# NODE_Misc_V2.net
KiCad netlist of a schematic drawn in Altium Designer
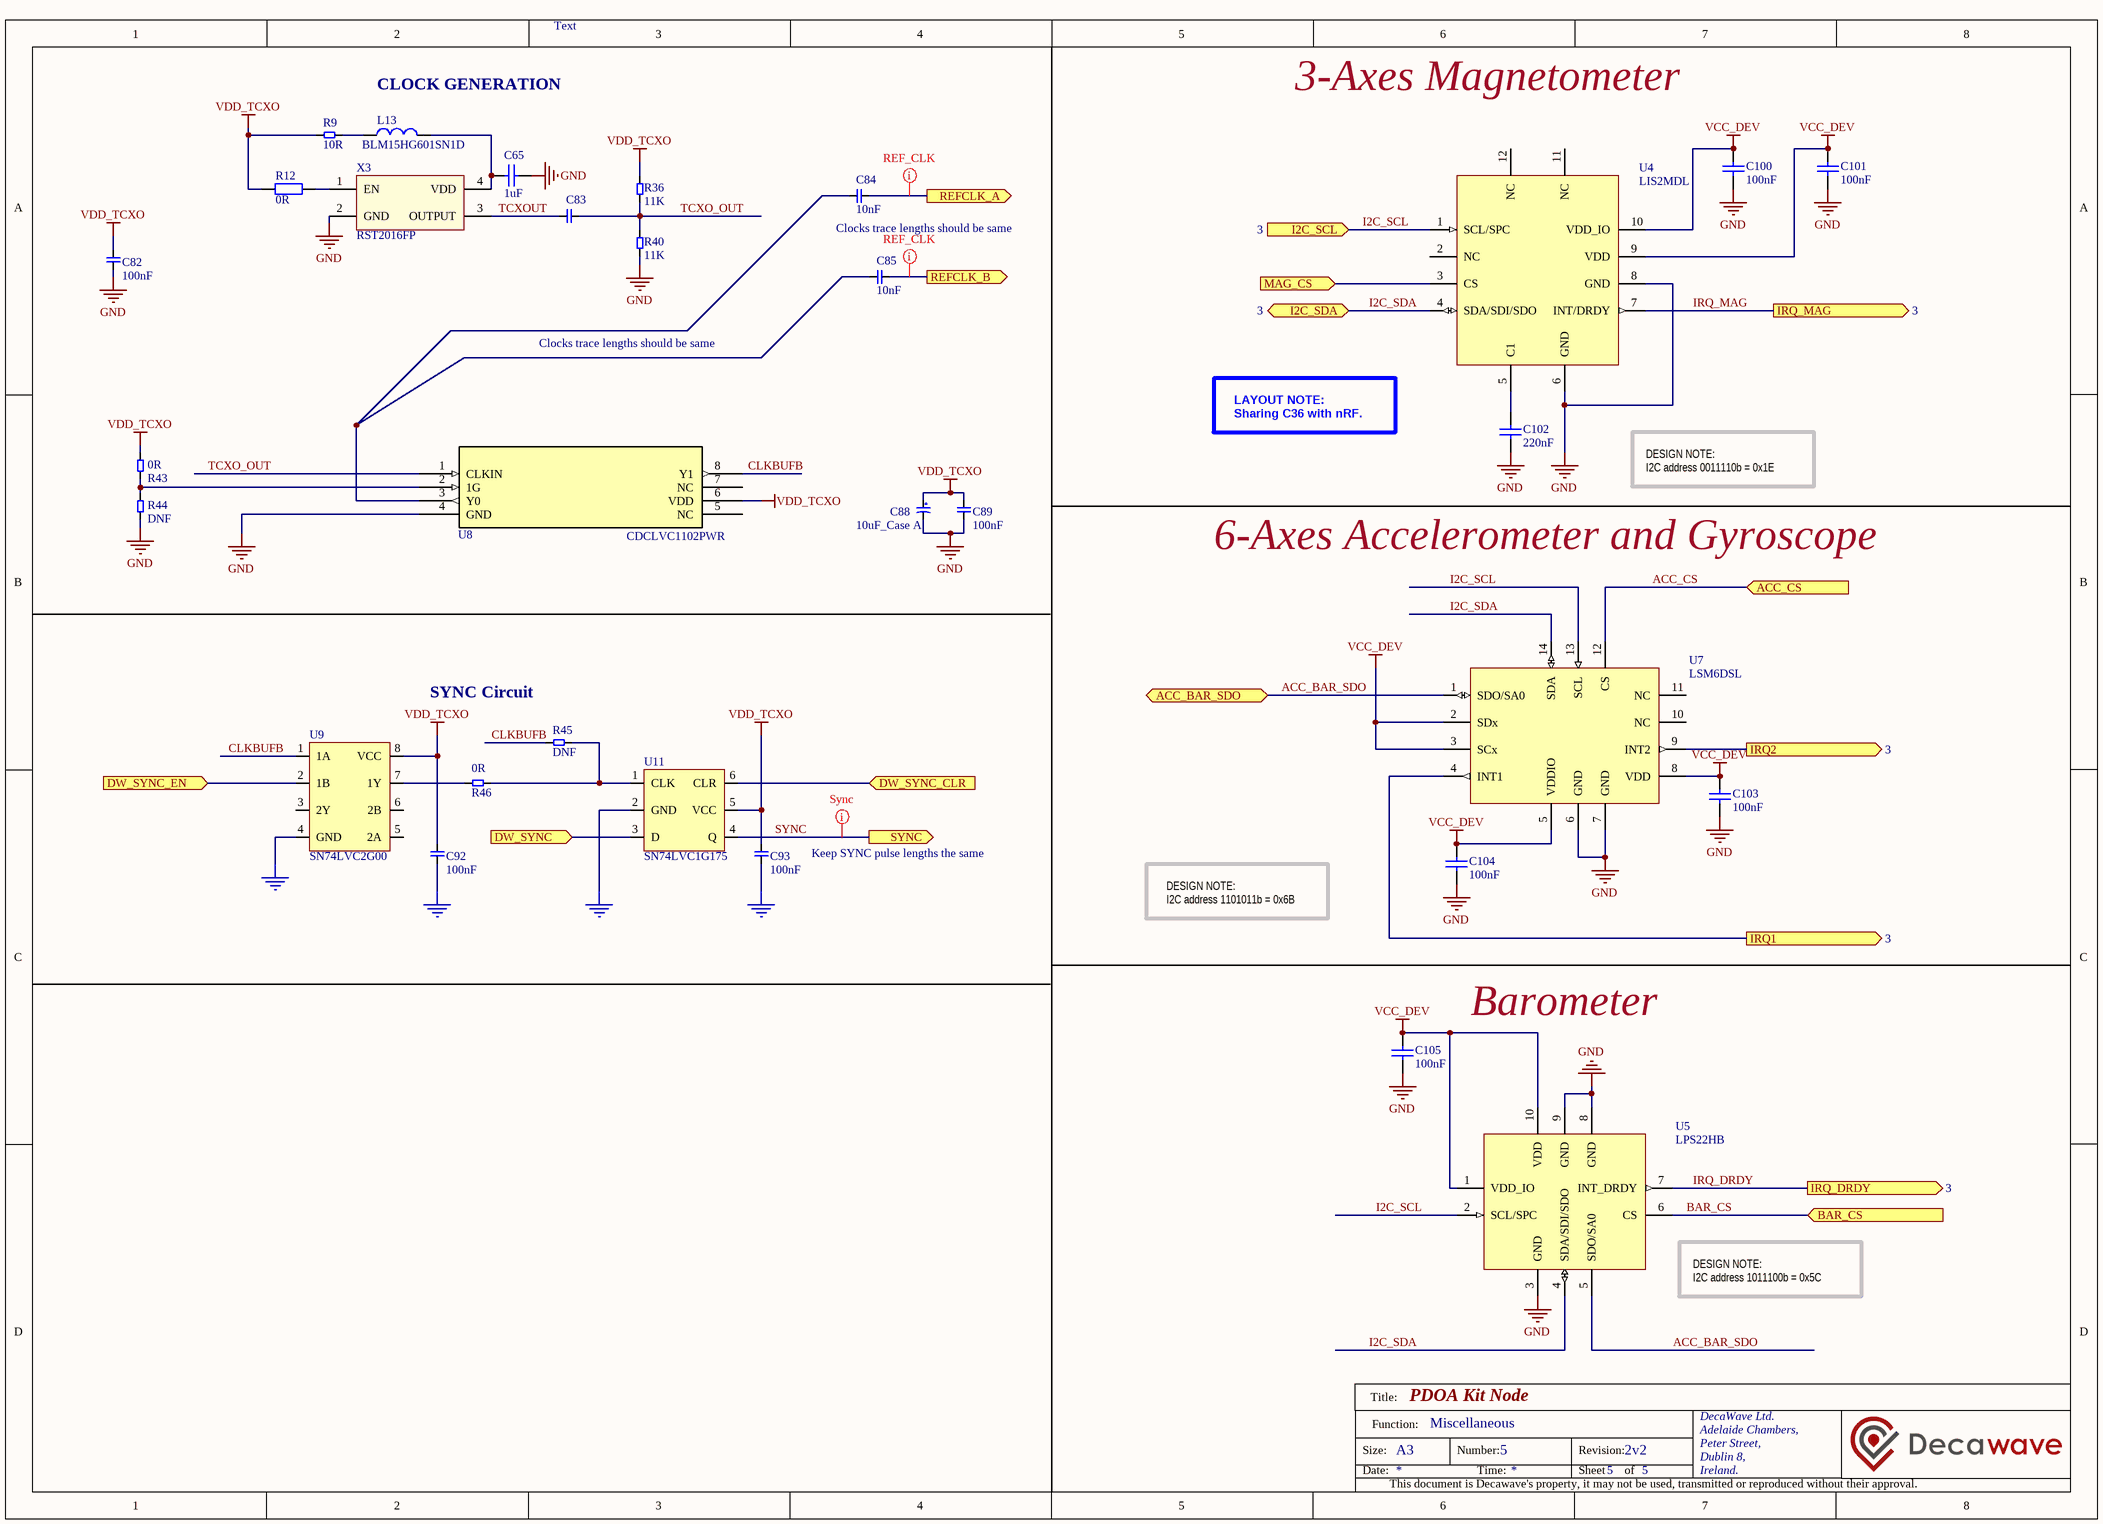
[diagram p0: NODE_Misc_V2.SchDoc]

(export (version "E")
  (design (tool "Eeschema 10.0.6"))
  (components
    (comp (ref "C65")
      (value "1uF")
      (footprint "C0402")
      (description "CAP CER 1UF 10V X5R 0402")
      (fields
        (field (name "MANUFACTURER") "Murata Electronics North America")
        (field (name "MANUFACTURER PART NUMBER") "GRM155R61A105KE15D")
      )
      (libsource (lib "drak_Library") (part "GRM155R61A105KE15D"))
    )
    (comp (ref "C82")
      (value "100nF")
      (footprint "C0201")
      (description "100nF_0201_10%")
      (fields
        (field (name "MANUFACTURER") "Murata Electronics North America")
        (field (name "MANUFACTURER PART NUMBER") "GRM033C81E104KE14D")
      )
      (libsource (lib "DecaWavedB") (part "Capacitor - non polarized"))
    )
    (comp (ref "C83")
      (value "1nF")
      (footprint "C0402")
      (description "1nF_0402_10%")
      (fields
        (field (name "MANUFACTURER PART NUMBER") "GRM155R71H102KA01D")
        (field (name "MANUFACTURER") "Murata Electronics North America")
      )
      (libsource (lib "DecaWavedB") (part "Capacitor - non polarized"))
    )
    (comp (ref "C84")
      (value "10nF")
      (footprint "C0201")
      (description "10nF_0201_10%")
      (fields
        (field (name "MANUFACTURER") "Murata Electronics North America")
        (field (name "MANUFACTURER PART NUMBER") "GRM033R61E103KA12D")
      )
      (libsource (lib "DecaWavedB") (part "Capacitor - non polarized"))
    )
    (comp (ref "C85")
      (value "10nF")
      (footprint "C0201")
      (description "10nF_0201_10%")
      (fields
        (field (name "MANUFACTURER") "Murata Electronics North America")
        (field (name "MANUFACTURER PART NUMBER") "GRM033R61E103KA12D")
      )
      (libsource (lib "DecaWavedB") (part "Capacitor - non polarized"))
    )
    (comp (ref "C88")
      (value "10uF_Case A")
      (footprint "TANT3216")
      (description "10uF_CaseA_10%")
      (fields
        (field (name "MANUFACTURER PART NUMBER") "293D106X9016A2TE3")
        (field (name "MANUFACTURER") "Vishay")
      )
      (libsource (lib "DecaWavedB") (part "Capacitor - polarized"))
    )
    (comp (ref "C89")
      (value "100nF")
      (footprint "C0201")
      (description "100nF_0201_10%")
      (fields
        (field (name "MANUFACTURER") "Murata Electronics North America")
        (field (name "MANUFACTURER PART NUMBER") "GRM033C81E104KE14D")
      )
      (libsource (lib "DecaWavedB") (part "Capacitor - non polarized"))
    )
    (comp (ref "C92")
      (value "100nF")
      (footprint "C0201")
      (description "100nF_0201_10%")
      (fields
        (field (name "MANUFACTURER") "Murata Electronics North America")
        (field (name "MANUFACTURER PART NUMBER") "GRM033C81E104KE14D")
      )
      (libsource (lib "DecaWavedB") (part "Capacitor - non polarized"))
    )
    (comp (ref "C93")
      (value "100nF")
      (footprint "C0201")
      (description "100nF_0201_10%")
      (fields
        (field (name "MANUFACTURER") "Murata Electronics North America")
        (field (name "MANUFACTURER PART NUMBER") "GRM033C81E104KE14D")
      )
      (libsource (lib "DecaWavedB") (part "Capacitor - non polarized"))
    )
    (comp (ref "C100")
      (value "100nF")
      (footprint "C0201")
      (description "100nF_0201_10%")
      (fields
        (field (name "MANUFACTURER") "Murata Electronics North America")
        (field (name "MANUFACTURER PART NUMBER") "GRM033C81E104KE14D")
      )
      (libsource (lib "drak_Library") (part "GRM033C81E104ME14D"))
    )
    (comp (ref "C101")
      (value "100nF")
      (footprint "C0201")
      (description "100nF_0201_10%")
      (fields
        (field (name "MANUFACTURER") "Murata Electronics North America")
        (field (name "MANUFACTURER PART NUMBER") "GRM033C81E104KE14D")
      )
      (libsource (lib "drak_Library") (part "GRM033C81E104ME14D"))
    )
    (comp (ref "C102")
      (value "220nF")
      (footprint "C0201")
      (description "CAP CER 220nF 25V X6S 0201")
      (fields
        (field (name "MANUFACTURER") "Murata Electronics North America")
        (field (name "MANUFACTURER PART NUMBER") "GRM033R61A224KE90D")
      )
      (libsource (lib "drak_Library") (part "GRM033C81E104ME14D"))
    )
    (comp (ref "C103")
      (value "100nF")
      (footprint "C0201")
      (description "100nF_0201_10%")
      (fields
        (field (name "MANUFACTURER") "Murata Electronics North America")
        (field (name "MANUFACTURER PART NUMBER") "GRM033C81E104KE14D")
      )
      (libsource (lib "drak_Library") (part "GRM033C81E104ME14D"))
    )
    (comp (ref "C104")
      (value "100nF")
      (footprint "C0201")
      (description "100nF_0201_10%")
      (fields
        (field (name "MANUFACTURER") "Murata Electronics North America")
        (field (name "MANUFACTURER PART NUMBER") "GRM033C81E104KE14D")
      )
      (libsource (lib "drak_Library") (part "GRM033C81E104ME14D"))
    )
    (comp (ref "C105")
      (value "100nF")
      (footprint "C0201")
      (description "100nF_0201_10%")
      (fields
        (field (name "MANUFACTURER") "Murata Electronics North America")
        (field (name "MANUFACTURER PART NUMBER") "GRM033C81E104KE14D")
      )
      (libsource (lib "drak_Library") (part "GRM033C81E104ME14D"))
    )
    (comp (ref "L13")
      (value "BLM15HG601SN1D")
      (footprint "L0402")
      (description "FERRITE BEAD, 0.7OHM, 300MA, 0402")
      (fields (field (name "MANUFACTURER") "Murata Electronics North America"))
      (libsource (lib "DecaWavedB") (part "inductor"))
    )
    (comp (ref "R9")
      (value "10R")
      (footprint "R0201")
      (description "10R_0201_1%")
      (fields
        (field (name "MANUFACTURER PART NUMBER") "RC0201FR-0710RL")
        (field (name "MANUFACTURER") "Yageo")
      )
      (libsource (lib "DecaWavedB") (part "Resistor"))
    )
    (comp (ref "R12")
      (value "0R")
      (footprint "R0201")
      (description "RES SMD 0.0OHM JUMPER 1/20W 0201")
      (fields
        (field (name "MANUFACTURER") "Yageo")
        (field (name "MANUFACTURER PART NUMBER") "RC0201JR-070RL")
      )
      (libsource (lib "drak_Library") (part "RC0201JR-070RL"))
    )
    (comp (ref "R36")
      (value "11K")
      (footprint "R0201")
      (description "11K_0201_1%")
      (fields
        (field (name "MANUFACTURER") "Yageo")
        (field (name "MANUFACTURER PART NUMBER") "RC0201FR-0711KL")
      )
      (libsource (lib "DecaWavedB") (part "Resistor"))
    )
    (comp (ref "R40")
      (value "11K")
      (footprint "R0201")
      (description "11K_0201_1%")
      (fields
        (field (name "MANUFACTURER") "Yageo")
        (field (name "MANUFACTURER PART NUMBER") "RC0201FR-0711KL")
      )
      (libsource (lib "DecaWavedB") (part "Resistor"))
    )
    (comp (ref "R43")
      (value "0R")
      (footprint "R0201")
      (description "RES SMD 0.0OHM JUMPER 1/20W 0201")
      (fields
        (field (name "MANUFACTURER PART NUMBER") "RC0201JR-070RL")
        (field (name "MANUFACTURER") "Yageo")
      )
      (libsource (lib "DecaWavedB") (part "Resistor"))
    )
    (comp (ref "R44") (value "DNF") (footprint "R0201") (libsource (lib "DecaWavedB") (part "Resistor")))
    (comp (ref "R45") (value "DNF") (footprint "R0201") (libsource (lib "DecaWavedB") (part "Resistor")))
    (comp (ref "R46")
      (value "0R")
      (footprint "R0201")
      (description "RES SMD 0.0OHM JUMPER 1/20W 0201")
      (fields
        (field (name "MANUFACTURER PART NUMBER") "RC0201JR-070RL")
        (field (name "MANUFACTURER") "Yageo")
      )
      (libsource (lib "DecaWavedB") (part "Resistor"))
    )
    (comp (ref "U4")
      (value "LIS2MDL")
      (footprint "IC_LGA-12")
      (fields
        (field (name "MANUFACTURER") "STmicroelectronics")
        (field (name "MANUFACTURER PART NUMBER") "LIS2MDLTR")
      )
      (libsource (lib "LGA12_LGA14_LIB") (part "LIS2MDL"))
    )
    (comp (ref "U5")
      (value "LPS22HB")
      (footprint "HLGA-10L")
      (fields
        (field (name "MANUFACTURER") "STmicroelectronics")
        (field (name "MANUFACTURER PART NUMBER") "LPS22HBTR")
      )
      (libsource (lib "LGA12_LGA14_LIB") (part "LPS22HB"))
    )
    (comp (ref "U7")
      (value "LSM6DSL")
      (footprint "IC_LGA-14")
      (fields
        (field (name "MANUFACTURER") "STmicroelectronics")
        (field (name "MANUFACTURER PART NUMBER") "LSM6DSLTR")
      )
      (libsource (lib "LGA12_LGA14_LIB") (part "LSM6DSL"))
    )
    (comp (ref "U8")
      (value "CDCLVC1102")
      (footprint "TSSOP8_0P65_4P5X3P4")
      (description "Low Jitter,1:2 LVCMOS Fan-out Clock Buffer")
      (fields (field (name "MANUFACTURER") "TI") (field (name "MANUFACTURER PART NUMBER") "CDCLVC1102PWR"))
      (libsource (lib "DecaWavedB") (part "CDCLVC1102"))
    )
    (comp (ref "U9")
      (value "SN74LVC2G00")
      (footprint "VSSOP8_0P5_2P1X2P4")
      (description "2 Input NAND")
      (fields (field (name "MANUFACTURER PART NUMBER") "SN74LVC2G00DCU") (field (name "MANUFACTURER") "TI"))
      (libsource (lib "DecaWavedB") (part "SN74LVC2G00"))
    )
    (comp (ref "U11")
      (value "SN74LVC1G175")
      (footprint "SC70-6_0P65_2P15X1P4")
      (description "Single D-Type Flip Flop with Async Clear")
      (fields (field (name "MANUFACTURER PART NUMBER") "SN74LVC1G175DCK") (field (name "MANUFACTURER") "TI"))
      (libsource (lib "DecaWavedB") (part "SN74LVC1G175"))
    )
    (comp (ref "X3")
      (value "RST2016FP")
      (footprint "CAT567")
      (description "CRYSTAL TXCO RST2016FP")
      (fields (field (name "MANUFACTURER") "Rakon"))
      (libsource (lib "LGA12_LGA14_LIB") (part "RST2016FP"))
    )
  )
  (nets
    (net (code "1") (name "/ACC_BAR_SDO") (class "Default")
      (node (ref "U5") (pin "5") (pinfunction "SDO/SA0_5") (pintype "passive"))
      (node (ref "U7") (pin "1") (pinfunction "SDO/SA0_1") (pintype "bidirectional"))
    )
    (net (code "2") (name "/ACC_CS") (class "Default")
      (node (ref "U7") (pin "12") (pinfunction "CS_12") (pintype "passive"))
    )
    (net (code "3") (name "/BAR_CS") (class "Default")
      (node (ref "U5") (pin "6") (pinfunction "CS_6") (pintype "passive"))
    )
    (net (code "4") (name "/CLKBUFB") (class "Default")
      (node (ref "R45") (pin "2") (pinfunction "2_2") (pintype "passive"))
      (node (ref "U8") (pin "8") (pinfunction "Y1_8") (pintype "output"))
      (node (ref "U9") (pin "1") (pinfunction "1A_1") (pintype "passive"))
    )
    (net (code "5") (name "/DW_SYNC") (class "Default")
      (node (ref "U11") (pin "3") (pinfunction "D_3") (pintype "passive"))
    )
    (net (code "6") (name "/DW_SYNC_CLR") (class "Default")
      (node (ref "U11") (pin "6") (pinfunction "CLR_6") (pintype "passive"))
    )
    (net (code "7") (name "/DW_SYNC_EN") (class "Default")
      (node (ref "U9") (pin "2") (pinfunction "1B_2") (pintype "passive"))
    )
    (net (code "8") (name "/I2C_SCL") (class "Default")
      (node (ref "U4") (pin "1") (pinfunction "SCL/SPC_1") (pintype "input"))
      (node (ref "U5") (pin "2") (pinfunction "SCL/SPC_2") (pintype "input"))
      (node (ref "U7") (pin "13") (pinfunction "SCL_13") (pintype "input"))
    )
    (net (code "9") (name "/I2C_SDA") (class "Default")
      (node (ref "U4") (pin "4") (pinfunction "SDA/SDI/SDO_4") (pintype "bidirectional"))
      (node (ref "U5") (pin "4") (pinfunction "SDA/SDI/SDO_4") (pintype "bidirectional"))
      (node (ref "U7") (pin "14") (pinfunction "SDA_14") (pintype "bidirectional"))
    )
    (net (code "10") (name "/IRQ1") (class "Default")
      (node (ref "U7") (pin "4") (pinfunction "INT1_4") (pintype "output"))
    )
    (net (code "11") (name "/IRQ2") (class "Default")
      (node (ref "U7") (pin "9") (pinfunction "INT2_9") (pintype "output"))
    )
    (net (code "12") (name "/IRQ_DRDY") (class "Default")
      (node (ref "U5") (pin "7") (pinfunction "INT_DRDY_7") (pintype "output"))
    )
    (net (code "13") (name "/IRQ_MAG") (class "Default")
      (node (ref "U4") (pin "7") (pinfunction "INT/DRDY_7") (pintype "output"))
    )
    (net (code "14") (name "/MAG_CS") (class "Default")
      (node (ref "U4") (pin "3") (pinfunction "CS_3") (pintype "passive"))
    )
    (net (code "15") (name "/REFCLK_A") (class "Default")
      (node (ref "C84") (pin "1") (pinfunction "1_1") (pintype "passive"))
    )
    (net (code "16") (name "/REFCLK_B") (class "Default")
      (node (ref "C85") (pin "1") (pinfunction "1_1") (pintype "passive"))
    )
    (net (code "17") (name "/SYNC") (class "Default")
      (node (ref "U11") (pin "4") (pinfunction "Q_4") (pintype "passive"))
    )
    (net (code "18") (name "/TCXOUT") (class "Default")
      (node (ref "C83") (pin "1") (pinfunction "1_1") (pintype "passive"))
      (node (ref "X3") (pin "3") (pinfunction "OUTPUT_3") (pintype "passive"))
    )
    (net (code "19") (name "/TCXO_OUT") (class "Default")
      (node (ref "C83") (pin "2") (pinfunction "2_2") (pintype "passive"))
      (node (ref "R36") (pin "1") (pinfunction "1_1") (pintype "passive"))
      (node (ref "R40") (pin "2") (pinfunction "2_2") (pintype "passive"))
      (node (ref "U8") (pin "1") (pinfunction "CLKIN_1") (pintype "input"))
    )
    (net (code "20") (name "GND") (class "Default")
      (node (ref "C100") (pin "1") (pinfunction "1_1") (pintype "passive"))
      (node (ref "C101") (pin "1") (pinfunction "1_1") (pintype "passive"))
      (node (ref "C102") (pin "1") (pinfunction "1_1") (pintype "passive"))
      (node (ref "C103") (pin "1") (pinfunction "1_1") (pintype "passive"))
      (node (ref "C104") (pin "1") (pinfunction "1_1") (pintype "passive"))
      (node (ref "C105") (pin "1") (pinfunction "1_1") (pintype "passive"))
      (node (ref "C65") (pin "1") (pinfunction "1_1") (pintype "passive"))
      (node (ref "C82") (pin "1") (pinfunction "1_1") (pintype "passive"))
      (node (ref "C88") (pin "2") (pinfunction "2_2") (pintype "passive"))
      (node (ref "C89") (pin "1") (pinfunction "1_1") (pintype "passive"))
      (node (ref "C92") (pin "1") (pinfunction "1_1") (pintype "passive"))
      (node (ref "C93") (pin "1") (pinfunction "1_1") (pintype "passive"))
      (node (ref "R40") (pin "1") (pinfunction "1_1") (pintype "passive"))
      (node (ref "R44") (pin "1") (pinfunction "1_1") (pintype "passive"))
      (node (ref "U11") (pin "2") (pinfunction "GND_2") (pintype "passive"))
      (node (ref "U4") (pin "6") (pinfunction "GND_6") (pintype "passive"))
      (node (ref "U4") (pin "8") (pinfunction "GND_8") (pintype "passive"))
      (node (ref "U5") (pin "3") (pinfunction "GND_3") (pintype "passive"))
      (node (ref "U5") (pin "8") (pinfunction "GND_8") (pintype "passive"))
      (node (ref "U5") (pin "9") (pinfunction "GND_9") (pintype "passive"))
      (node (ref "U7") (pin "6") (pinfunction "GND_6") (pintype "passive"))
      (node (ref "U7") (pin "7") (pinfunction "GND_7") (pintype "passive"))
      (node (ref "U8") (pin "4") (pinfunction "GND_4") (pintype "power_in"))
      (node (ref "U9") (pin "4") (pinfunction "GND_4") (pintype "passive"))
      (node (ref "X3") (pin "2") (pinfunction "GND_2") (pintype "passive"))
    )
    (net (code "21") (name "Net-(L13-Pad1)") (class "Default")
      (node (ref "L13") (pin "1") (pinfunction "1_1") (pintype "passive"))
      (node (ref "R9") (pin "1") (pinfunction "1_1") (pintype "passive"))
    )
    (net (code "22") (name "Net-(U4-C1)") (class "Default")
      (node (ref "C102") (pin "2") (pinfunction "2_2") (pintype "passive"))
      (node (ref "U4") (pin "5") (pinfunction "C1_5") (pintype "passive"))
    )
    (net (code "23") (name "Net-(U8-1G)") (class "Default")
      (node (ref "R43") (pin "2") (pinfunction "2_2") (pintype "passive"))
      (node (ref "R44") (pin "2") (pinfunction "2_2") (pintype "passive"))
      (node (ref "U8") (pin "2") (pinfunction "1G_2") (pintype "input"))
    )
    (net (code "24") (name "Net-(U8-Y0)") (class "Default")
      (node (ref "C84") (pin "2") (pinfunction "2_2") (pintype "passive"))
      (node (ref "C85") (pin "2") (pinfunction "2_2") (pintype "passive"))
      (node (ref "U8") (pin "3") (pinfunction "Y0_3") (pintype "output"))
    )
    (net (code "25") (name "Net-(U9-1Y)") (class "Default")
      (node (ref "R46") (pin "2") (pinfunction "2_2") (pintype "passive"))
      (node (ref "U9") (pin "7") (pinfunction "1Y_7") (pintype "passive"))
    )
    (net (code "26") (name "Net-(U11-CLK)") (class "Default")
      (node (ref "R45") (pin "1") (pinfunction "1_1") (pintype "passive"))
      (node (ref "R46") (pin "1") (pinfunction "1_1") (pintype "passive"))
      (node (ref "U11") (pin "1") (pinfunction "CLK_1") (pintype "passive"))
    )
    (net (code "27") (name "Net-(X3-EN)") (class "Default")
      (node (ref "R12") (pin "2") (pinfunction "2_2") (pintype "passive"))
      (node (ref "X3") (pin "1") (pinfunction "EN_1") (pintype "passive"))
    )
    (net (code "28") (name "Net-(X3-VDD)") (class "Default")
      (node (ref "C65") (pin "2") (pinfunction "2_2") (pintype "passive"))
      (node (ref "L13") (pin "2") (pinfunction "2_2") (pintype "passive"))
      (node (ref "X3") (pin "4") (pinfunction "VDD_4") (pintype "passive"))
    )
    (net (code "29") (name "VCC_DEV") (class "Default")
      (node (ref "C100") (pin "2") (pinfunction "2_2") (pintype "passive"))
      (node (ref "C101") (pin "2") (pinfunction "2_2") (pintype "passive"))
      (node (ref "C103") (pin "2") (pinfunction "2_2") (pintype "passive"))
      (node (ref "C104") (pin "2") (pinfunction "2_2") (pintype "passive"))
      (node (ref "C105") (pin "2") (pinfunction "2_2") (pintype "passive"))
      (node (ref "U4") (pin "10") (pinfunction "VDD_IO_10") (pintype "power_in"))
      (node (ref "U4") (pin "9") (pinfunction "VDD_9") (pintype "power_in"))
      (node (ref "U5") (pin "1") (pinfunction "VDD_IO_1") (pintype "power_in"))
      (node (ref "U5") (pin "10") (pinfunction "VDD_10") (pintype "power_in"))
      (node (ref "U7") (pin "2") (pinfunction "SDx_2") (pintype "passive"))
      (node (ref "U7") (pin "3") (pinfunction "SCx_3") (pintype "passive"))
      (node (ref "U7") (pin "5") (pinfunction "VDDIO_5") (pintype "power_in"))
      (node (ref "U7") (pin "8") (pinfunction "VDD_8") (pintype "power_in"))
    )
    (net (code "30") (name "VDD_TCXO") (class "Default")
      (node (ref "C82") (pin "2") (pinfunction "2_2") (pintype "passive"))
      (node (ref "C88") (pin "1") (pinfunction "1_1") (pintype "passive"))
      (node (ref "C89") (pin "2") (pinfunction "2_2") (pintype "passive"))
      (node (ref "C92") (pin "2") (pinfunction "2_2") (pintype "passive"))
      (node (ref "C93") (pin "2") (pinfunction "2_2") (pintype "passive"))
      (node (ref "R12") (pin "1") (pinfunction "1_1") (pintype "passive"))
      (node (ref "R36") (pin "2") (pinfunction "2_2") (pintype "passive"))
      (node (ref "R43") (pin "1") (pinfunction "1_1") (pintype "passive"))
      (node (ref "R9") (pin "2") (pinfunction "2_2") (pintype "passive"))
      (node (ref "U11") (pin "5") (pinfunction "VCC_5") (pintype "passive"))
      (node (ref "U8") (pin "6") (pinfunction "VDD_6") (pintype "power_in"))
      (node (ref "U9") (pin "8") (pinfunction "VCC_8") (pintype "passive"))
    )
    (net (code "31") (name "unconnected-(U4-NC-Pad2)") (class "Default")
      (node (ref "U4") (pin "2") (pinfunction "NC_2") (pintype "passive"))
    )
    (net (code "32") (name "unconnected-(U4-NC-Pad11)") (class "Default")
      (node (ref "U4") (pin "11") (pinfunction "NC_11") (pintype "passive"))
    )
    (net (code "33") (name "unconnected-(U4-NC-Pad12)") (class "Default")
      (node (ref "U4") (pin "12") (pinfunction "NC_12") (pintype "passive"))
    )
    (net (code "34") (name "unconnected-(U7-NC-Pad10)") (class "Default")
      (node (ref "U7") (pin "10") (pinfunction "NC_10") (pintype "passive"))
    )
    (net (code "35") (name "unconnected-(U7-NC-Pad11)") (class "Default")
      (node (ref "U7") (pin "11") (pinfunction "NC_11") (pintype "passive"))
    )
    (net (code "36") (name "unconnected-(U8-NC-Pad5)") (class "Default")
      (node (ref "U8") (pin "5") (pinfunction "NC_5") (pintype "power_in"))
    )
    (net (code "37") (name "unconnected-(U8-NC-Pad7)") (class "Default")
      (node (ref "U8") (pin "7") (pinfunction "NC_7") (pintype "power_in"))
    )
    (net (code "38") (name "unconnected-(U9-2A-Pad5)") (class "Default")
      (node (ref "U9") (pin "5") (pinfunction "2A_5") (pintype "passive"))
    )
    (net (code "39") (name "unconnected-(U9-2B-Pad6)") (class "Default")
      (node (ref "U9") (pin "6") (pinfunction "2B_6") (pintype "passive"))
    )
    (net (code "40") (name "unconnected-(U9-2Y-Pad3)") (class "Default")
      (node (ref "U9") (pin "3") (pinfunction "2Y_3") (pintype "passive"))
    )
  )
)
